# Power.net
KiCad netlist of a schematic drawn in Altium Designer
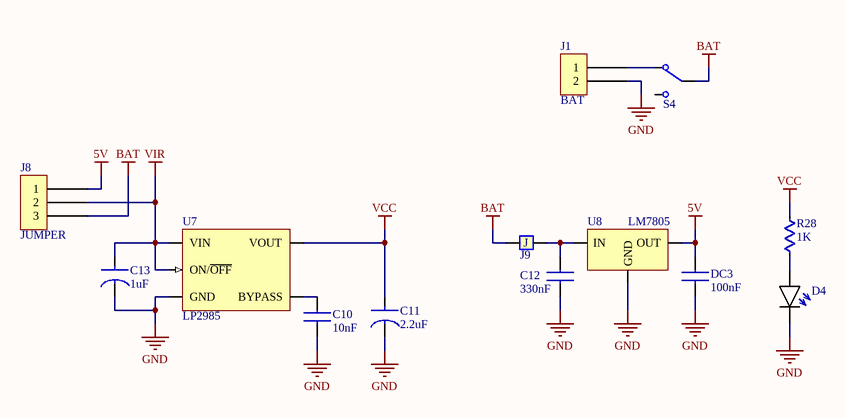
[diagram p0: Power.SchDoc]

(export (version "E")
  (design (tool "Eeschema 10.0.6"))
  (components
    (comp (ref "C10")
      (value "10nF")
      (footprint "C1206")
      (fields (field (name "Comment") "CAP-CER"))
      (libsource (lib "AltiumLibrary") (part "CAP-CER"))
    )
    (comp (ref "C11")
      (value "2.2uF")
      (footprint "CAP-ELEC-5x11x2mm")
      (fields (field (name "Comment") "CAP-ELEC"))
      (libsource (lib "AltiumLibrary") (part "CAP-ELEC"))
    )
    (comp (ref "C12")
      (value "330nF")
      (footprint "C1206")
      (fields (field (name "Comment") "CAP-CER"))
      (libsource (lib "AltiumLibrary") (part "CAP-CER"))
    )
    (comp (ref "C13")
      (value "1uF")
      (footprint "CAP-ELEC-5x11x2mm")
      (fields (field (name "Comment") "CAP-ELEC"))
      (libsource (lib "AltiumLibrary") (part "CAP-ELEC"))
    )
    (comp (ref "D4") (value "LED") (footprint "LED-3MM-RED") (libsource (lib "AltiumLibrary") (part "LED")))
    (comp (ref "DC3")
      (value "100nF")
      (footprint "C1206")
      (fields (field (name "Comment") "CAP-CER"))
      (libsource (lib "AltiumLibrary") (part "CAP-CER"))
    )
    (comp (ref "J1")
      (value "BAT")
      (footprint "HEADER 1x2")
      (libsource (lib "AltiumLibrary") (part "Header 1x2"))
    )
    (comp (ref "J8")
      (value "JUMPER")
      (footprint "Header 1x3")
      (libsource (lib "AltiumLibrary") (part "Header 1x3"))
    )
    (comp (ref "J9") (value "JUMPER") (footprint "JUMPER") (libsource (lib "AltiumLibrary") (part "JUMPER")))
    (comp (ref "R28")
      (value "1K")
      (footprint "R1206")
      (fields (field (name "Comment") "RES"))
      (libsource (lib "AltiumLibrary") (part "RES"))
    )
    (comp (ref "S4")
      (value "SLIDE-SWITCH")
      (footprint "SWITCH")
      (libsource (lib "AltiumLibrary") (part "SLIDE-SWITCH"))
    )
    (comp (ref "U7")
      (value "LP2985")
      (footprint "SOT-23-5")
      (libsource (lib "AltiumLibrary") (part "LP2985"))
    )
    (comp (ref "U8")
      (value "LM7805")
      (footprint "TO-220-FLAT")
      (libsource (lib "AltiumLibrary") (part "LM78XX"))
    )
  )
  (nets
    (net (code "1") (name "5V") (class "Default")
      (node (ref "DC3") (pin "2") (pintype "passive"))
      (node (ref "J8") (pin "1") (pinfunction "1_1") (pintype "passive"))
      (node (ref "U8") (pin "3") (pinfunction "OUT_3") (pintype "power_in"))
    )
    (net (code "2") (name "BAT") (class "Default")
      (node (ref "J8") (pin "3") (pinfunction "3_3") (pintype "passive"))
      (node (ref "J9") (pin "2") (pintype "passive"))
      (node (ref "S4") (pin "2") (pintype "power_in"))
    )
    (net (code "3") (name "GND") (class "Default")
      (node (ref "C10") (pin "1") (pintype "passive"))
      (node (ref "C11") (pin "2") (pintype "passive"))
      (node (ref "C12") (pin "2") (pintype "passive"))
      (node (ref "C13") (pin "2") (pintype "passive"))
      (node (ref "D4") (pin "K") (pintype "passive"))
      (node (ref "DC3") (pin "1") (pintype "passive"))
      (node (ref "J1") (pin "2") (pinfunction "2_2") (pintype "passive"))
      (node (ref "U7") (pin "2") (pinfunction "GND_2") (pintype "power_in"))
      (node (ref "U8") (pin "2") (pinfunction "GND_2") (pintype "power_in"))
    )
    (net (code "4") (name "Net-(D4-PadA)") (class "Default")
      (node (ref "D4") (pin "A") (pintype "passive"))
      (node (ref "R28") (pin "1") (pintype "passive"))
    )
    (net (code "5") (name "Net-(J1-Pad1)") (class "Default")
      (node (ref "J1") (pin "1") (pinfunction "1_1") (pintype "passive"))
      (node (ref "S4") (pin "1") (pintype "power_in"))
    )
    (net (code "6") (name "Net-(U7-BYPASS)") (class "Default")
      (node (ref "C10") (pin "2") (pintype "passive"))
      (node (ref "U7") (pin "4") (pinfunction "BYPASS_4") (pintype "passive"))
    )
    (net (code "7") (name "Net-(U8-IN)") (class "Default")
      (node (ref "C12") (pin "1") (pintype "passive"))
      (node (ref "J9") (pin "1") (pintype "passive"))
      (node (ref "U8") (pin "1") (pinfunction "IN_1") (pintype "power_in"))
    )
    (net (code "8") (name "VCC") (class "Default")
      (node (ref "C11") (pin "1") (pintype "passive"))
      (node (ref "R28") (pin "2") (pintype "passive"))
      (node (ref "U7") (pin "5") (pinfunction "VOUT_5") (pintype "passive"))
    )
    (net (code "9") (name "VIR") (class "Default")
      (node (ref "C13") (pin "1") (pintype "passive"))
      (node (ref "J8") (pin "2") (pinfunction "2_2") (pintype "passive"))
      (node (ref "U7") (pin "1") (pinfunction "VIN_1") (pintype "power_in"))
      (node (ref "U7") (pin "3") (pinfunction "ON/~{OFF}_3") (pintype "input"))
    )
    (net (code "10") (name "unconnected-(S4-Pad3)") (class "Default")
      (node (ref "S4") (pin "3") (pintype "power_in"))
    )
  )
)
